# PCB_SCH_Right_Sub.net
KiCad netlist of a schematic drawn in EasyEDA Pro
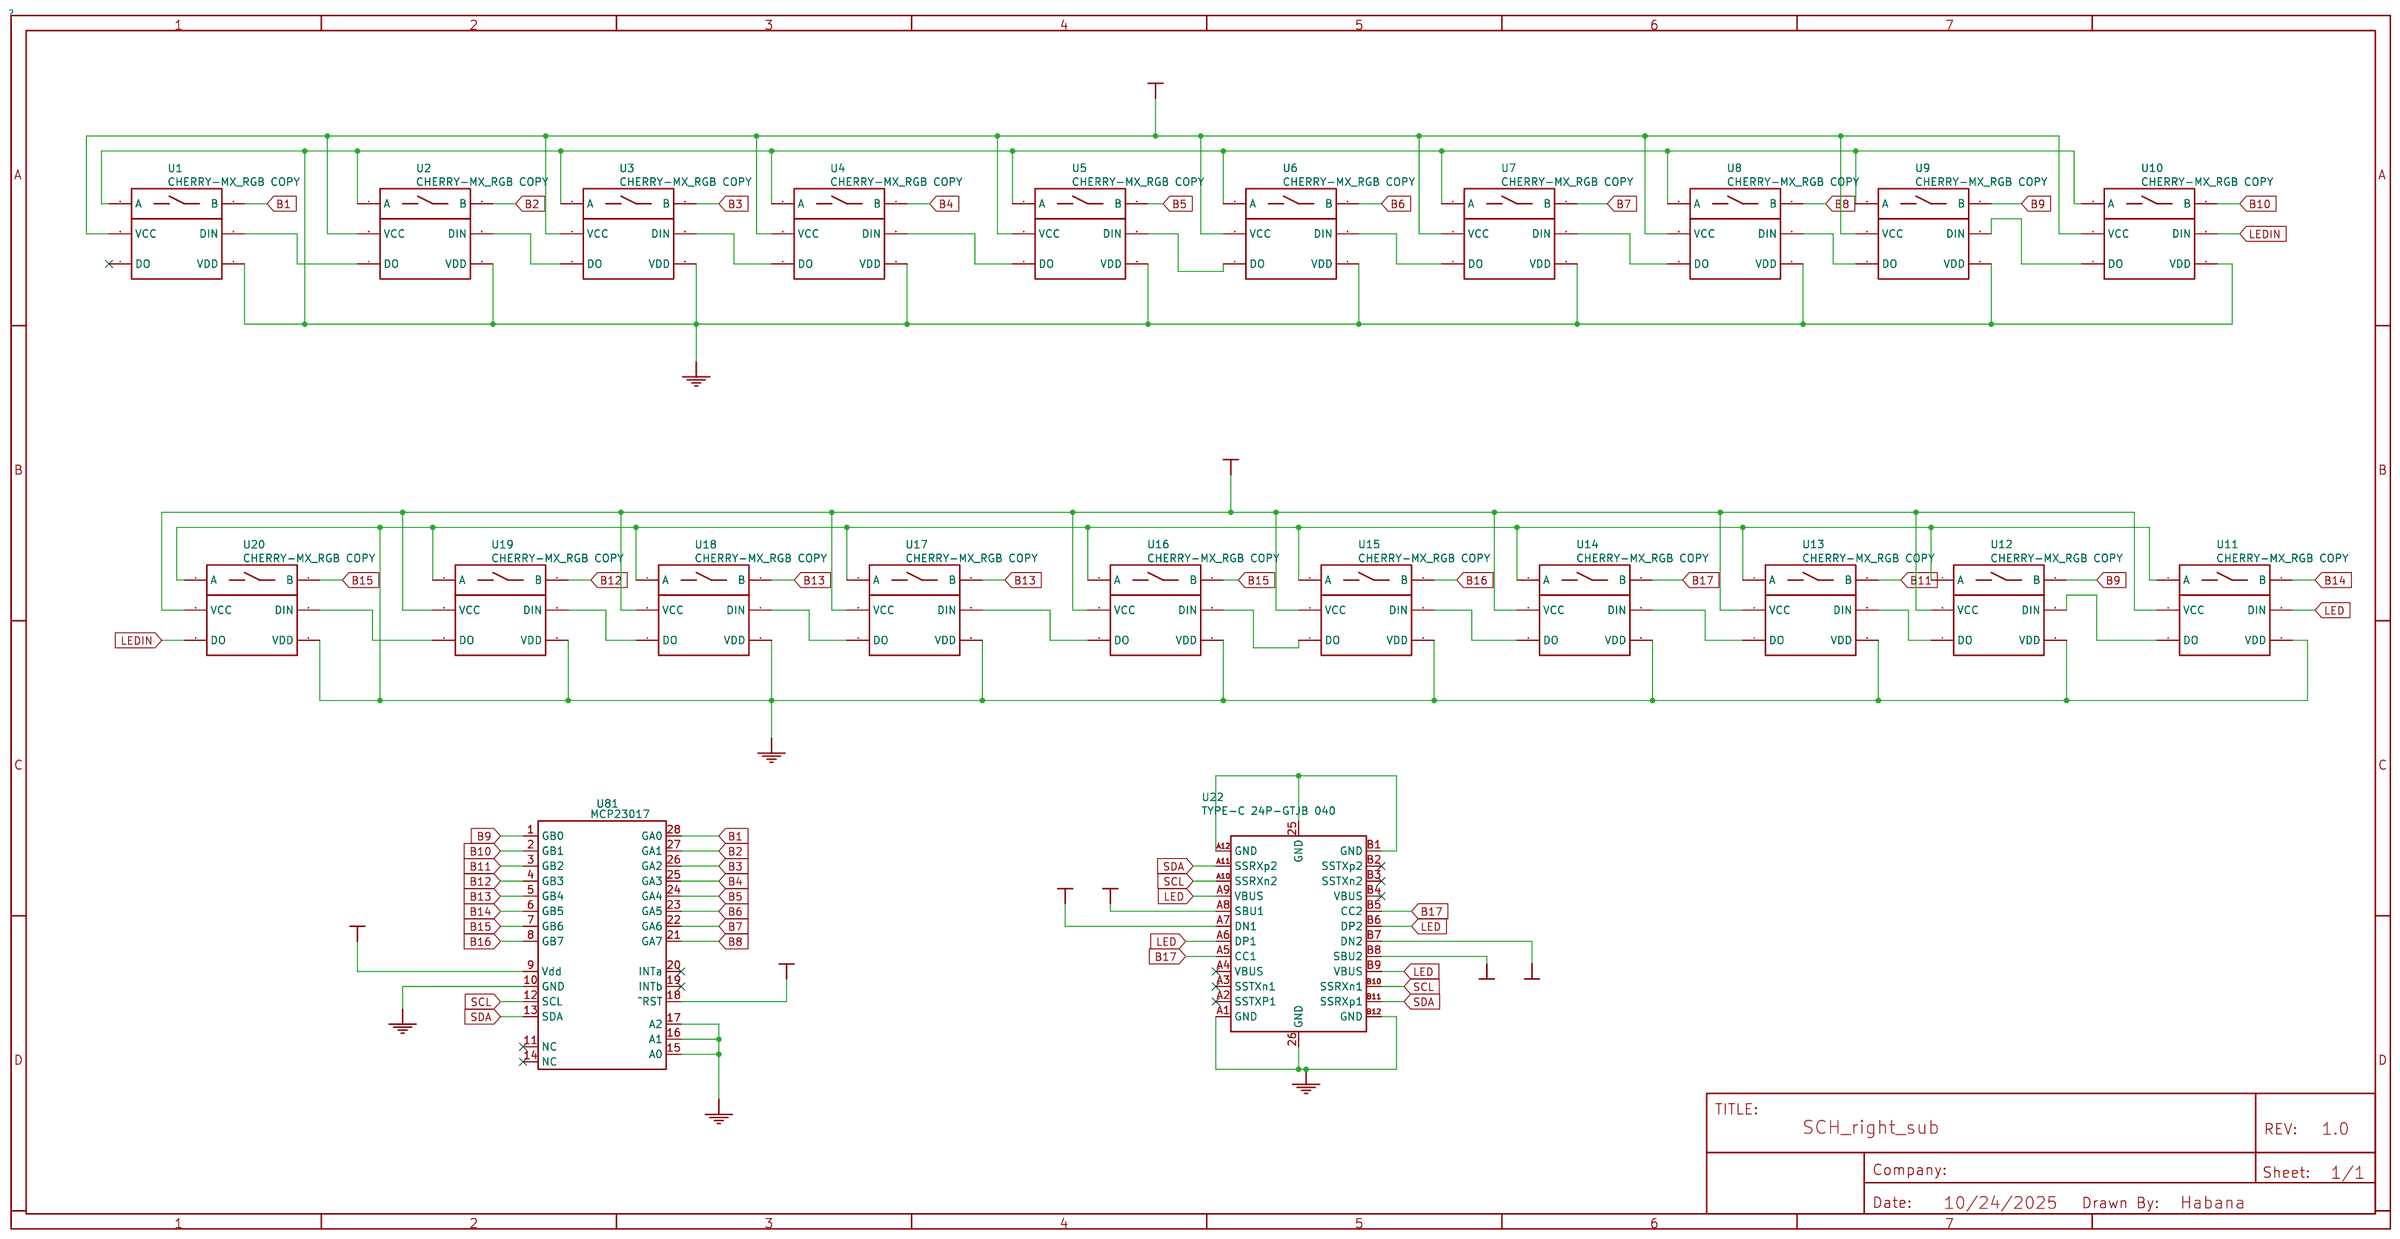
[diagram p0: schematic sheet]

(export (version "E")
  (design (tool "Eeschema 10.0.6"))
  (components
    (comp (ref "U1")
      (value "CHERRY-MX_RGB COPY")
      (fields (field (name "Contributor") "unrealin01"))
      (libsource (lib "easyedapro") (part "CHERRY-MX_RGB COPY"))
    )
    (comp (ref "U2")
      (value "CHERRY-MX_RGB COPY")
      (fields (field (name "Contributor") "unrealin01"))
      (libsource (lib "easyedapro") (part "CHERRY-MX_RGB COPY"))
    )
    (comp (ref "U3")
      (value "CHERRY-MX_RGB COPY")
      (fields (field (name "Contributor") "unrealin01"))
      (libsource (lib "easyedapro") (part "CHERRY-MX_RGB COPY"))
    )
    (comp (ref "U4")
      (value "CHERRY-MX_RGB COPY")
      (fields (field (name "Contributor") "unrealin01"))
      (libsource (lib "easyedapro") (part "CHERRY-MX_RGB COPY"))
    )
    (comp (ref "U5")
      (value "CHERRY-MX_RGB COPY")
      (fields (field (name "Contributor") "unrealin01"))
      (libsource (lib "easyedapro") (part "CHERRY-MX_RGB COPY"))
    )
    (comp (ref "U6")
      (value "CHERRY-MX_RGB COPY")
      (fields (field (name "Contributor") "unrealin01"))
      (libsource (lib "easyedapro") (part "CHERRY-MX_RGB COPY"))
    )
    (comp (ref "U7")
      (value "CHERRY-MX_RGB COPY")
      (fields (field (name "Contributor") "unrealin01"))
      (libsource (lib "easyedapro") (part "CHERRY-MX_RGB COPY"))
    )
    (comp (ref "U8")
      (value "CHERRY-MX_RGB COPY")
      (fields (field (name "Contributor") "unrealin01"))
      (libsource (lib "easyedapro") (part "CHERRY-MX_RGB COPY"))
    )
    (comp (ref "U9")
      (value "CHERRY-MX_RGB COPY")
      (fields (field (name "Contributor") "unrealin01"))
      (libsource (lib "easyedapro") (part "CHERRY-MX_RGB COPY"))
    )
    (comp (ref "U10")
      (value "CHERRY-MX_RGB COPY")
      (fields (field (name "Contributor") "unrealin01"))
      (libsource (lib "easyedapro") (part "CHERRY-MX_RGB COPY"))
    )
    (comp (ref "U11")
      (value "CHERRY-MX_RGB COPY")
      (fields (field (name "Contributor") "unrealin01"))
      (libsource (lib "easyedapro") (part "CHERRY-MX_RGB COPY"))
    )
    (comp (ref "U12")
      (value "CHERRY-MX_RGB COPY")
      (fields (field (name "Contributor") "unrealin01"))
      (libsource (lib "easyedapro") (part "CHERRY-MX_RGB COPY"))
    )
    (comp (ref "U13")
      (value "CHERRY-MX_RGB COPY")
      (fields (field (name "Contributor") "unrealin01"))
      (libsource (lib "easyedapro") (part "CHERRY-MX_RGB COPY"))
    )
    (comp (ref "U14")
      (value "CHERRY-MX_RGB COPY")
      (fields (field (name "Contributor") "unrealin01"))
      (libsource (lib "easyedapro") (part "CHERRY-MX_RGB COPY"))
    )
    (comp (ref "U15")
      (value "CHERRY-MX_RGB COPY")
      (fields (field (name "Contributor") "unrealin01"))
      (libsource (lib "easyedapro") (part "CHERRY-MX_RGB COPY"))
    )
    (comp (ref "U16")
      (value "CHERRY-MX_RGB COPY")
      (fields (field (name "Contributor") "unrealin01"))
      (libsource (lib "easyedapro") (part "CHERRY-MX_RGB COPY"))
    )
    (comp (ref "U17")
      (value "CHERRY-MX_RGB COPY")
      (fields (field (name "Contributor") "unrealin01"))
      (libsource (lib "easyedapro") (part "CHERRY-MX_RGB COPY"))
    )
    (comp (ref "U18")
      (value "CHERRY-MX_RGB COPY")
      (fields (field (name "Contributor") "unrealin01"))
      (libsource (lib "easyedapro") (part "CHERRY-MX_RGB COPY"))
    )
    (comp (ref "U19")
      (value "CHERRY-MX_RGB COPY")
      (fields (field (name "Contributor") "unrealin01"))
      (libsource (lib "easyedapro") (part "CHERRY-MX_RGB COPY"))
    )
    (comp (ref "U20")
      (value "CHERRY-MX_RGB COPY")
      (fields (field (name "Contributor") "unrealin01"))
      (libsource (lib "easyedapro") (part "CHERRY-MX_RGB COPY"))
    )
    (comp (ref "U22")
      (value "TYPE-C 24P-GTJB 040")
      (footprint "easyedapro:USB-C-SMD_TYPE-C-24P-GTJB-040")
      (fields (field (name "Manufacturer") "SHOU HAN(首韩)") (field (name "Contributor") "lcsc"))
      (libsource (lib "easyedapro") (part "TYPE-C 24P-GTJB 040"))
    )
    (comp (ref "U81")
      (value "MCP23017")
      (fields (field (name "Contributor") "tsvstar"))
      (libsource (lib "easyedapro") (part "MCP23017"))
    )
  )
  (nets
    (net (code "1") (name "+5V") (class "Default")
      (node (ref "U1") (pin "3") (pinfunction "VCC_3") (pintype "unspecified"))
      (node (ref "U10") (pin "3") (pinfunction "VCC_3") (pintype "unspecified"))
      (node (ref "U11") (pin "3") (pinfunction "VCC_3") (pintype "unspecified"))
      (node (ref "U12") (pin "3") (pinfunction "VCC_3") (pintype "unspecified"))
      (node (ref "U13") (pin "3") (pinfunction "VCC_3") (pintype "unspecified"))
      (node (ref "U14") (pin "3") (pinfunction "VCC_3") (pintype "unspecified"))
      (node (ref "U15") (pin "3") (pinfunction "VCC_3") (pintype "unspecified"))
      (node (ref "U16") (pin "3") (pinfunction "VCC_3") (pintype "unspecified"))
      (node (ref "U17") (pin "3") (pinfunction "VCC_3") (pintype "unspecified"))
      (node (ref "U18") (pin "3") (pinfunction "VCC_3") (pintype "unspecified"))
      (node (ref "U19") (pin "3") (pinfunction "VCC_3") (pintype "unspecified"))
      (node (ref "U2") (pin "3") (pinfunction "VCC_3") (pintype "unspecified"))
      (node (ref "U20") (pin "3") (pinfunction "VCC_3") (pintype "unspecified"))
      (node (ref "U22") (pin "A8") (pinfunction "SBU1_A8") (pintype "unspecified"))
      (node (ref "U22") (pin "B8") (pinfunction "SBU2_B8") (pintype "unspecified"))
      (node (ref "U3") (pin "3") (pinfunction "VCC_3") (pintype "unspecified"))
      (node (ref "U4") (pin "3") (pinfunction "VCC_3") (pintype "unspecified"))
      (node (ref "U5") (pin "3") (pinfunction "VCC_3") (pintype "unspecified"))
      (node (ref "U6") (pin "3") (pinfunction "VCC_3") (pintype "unspecified"))
      (node (ref "U7") (pin "3") (pinfunction "VCC_3") (pintype "unspecified"))
      (node (ref "U8") (pin "3") (pinfunction "VCC_3") (pintype "unspecified"))
      (node (ref "U9") (pin "3") (pinfunction "VCC_3") (pintype "unspecified"))
    )
    (net (code "2") (name "B1") (class "Default")
      (node (ref "U1") (pin "2") (pinfunction "B_2") (pintype "unspecified"))
      (node (ref "U81") (pin "28") (pinfunction "GA0_28") (pintype "unspecified"))
    )
    (net (code "3") (name "B2") (class "Default")
      (node (ref "U2") (pin "2") (pinfunction "B_2") (pintype "unspecified"))
      (node (ref "U81") (pin "27") (pinfunction "GA1_27") (pintype "unspecified"))
    )
    (net (code "4") (name "B3") (class "Default")
      (node (ref "U3") (pin "2") (pinfunction "B_2") (pintype "unspecified"))
      (node (ref "U81") (pin "26") (pinfunction "GA2_26") (pintype "unspecified"))
    )
    (net (code "5") (name "B4") (class "Default")
      (node (ref "U4") (pin "2") (pinfunction "B_2") (pintype "unspecified"))
      (node (ref "U81") (pin "25") (pinfunction "GA3_25") (pintype "unspecified"))
    )
    (net (code "6") (name "B5") (class "Default")
      (node (ref "U5") (pin "2") (pinfunction "B_2") (pintype "unspecified"))
      (node (ref "U81") (pin "24") (pinfunction "GA4_24") (pintype "unspecified"))
    )
    (net (code "7") (name "B6") (class "Default")
      (node (ref "U6") (pin "2") (pinfunction "B_2") (pintype "unspecified"))
      (node (ref "U81") (pin "23") (pinfunction "GA5_23") (pintype "unspecified"))
    )
    (net (code "8") (name "B7") (class "Default")
      (node (ref "U7") (pin "2") (pinfunction "B_2") (pintype "unspecified"))
      (node (ref "U81") (pin "22") (pinfunction "GA6_22") (pintype "unspecified"))
    )
    (net (code "9") (name "B8") (class "Default")
      (node (ref "U8") (pin "2") (pinfunction "B_2") (pintype "unspecified"))
      (node (ref "U81") (pin "21") (pinfunction "GA7_21") (pintype "unspecified"))
    )
    (net (code "10") (name "B9") (class "Default")
      (node (ref "U12") (pin "2") (pinfunction "B_2") (pintype "unspecified"))
      (node (ref "U81") (pin "1") (pinfunction "GB0_1") (pintype "unspecified"))
      (node (ref "U9") (pin "2") (pinfunction "B_2") (pintype "unspecified"))
    )
    (net (code "11") (name "B10") (class "Default")
      (node (ref "U10") (pin "2") (pinfunction "B_2") (pintype "unspecified"))
      (node (ref "U81") (pin "2") (pinfunction "GB1_2") (pintype "unspecified"))
    )
    (net (code "12") (name "B11") (class "Default")
      (node (ref "U13") (pin "2") (pinfunction "B_2") (pintype "unspecified"))
      (node (ref "U81") (pin "3") (pinfunction "GB2_3") (pintype "unspecified"))
    )
    (net (code "13") (name "B12") (class "Default")
      (node (ref "U19") (pin "2") (pinfunction "B_2") (pintype "unspecified"))
      (node (ref "U81") (pin "4") (pinfunction "GB3_4") (pintype "unspecified"))
    )
    (net (code "14") (name "B13") (class "Default")
      (node (ref "U17") (pin "2") (pinfunction "B_2") (pintype "unspecified"))
      (node (ref "U18") (pin "2") (pinfunction "B_2") (pintype "unspecified"))
      (node (ref "U81") (pin "5") (pinfunction "GB4_5") (pintype "unspecified"))
    )
    (net (code "15") (name "B14") (class "Default")
      (node (ref "U11") (pin "2") (pinfunction "B_2") (pintype "unspecified"))
      (node (ref "U81") (pin "6") (pinfunction "GB5_6") (pintype "unspecified"))
    )
    (net (code "16") (name "B15") (class "Default")
      (node (ref "U16") (pin "2") (pinfunction "B_2") (pintype "unspecified"))
      (node (ref "U20") (pin "2") (pinfunction "B_2") (pintype "unspecified"))
      (node (ref "U81") (pin "7") (pinfunction "GB6_7") (pintype "unspecified"))
    )
    (net (code "17") (name "B16") (class "Default")
      (node (ref "U15") (pin "2") (pinfunction "B_2") (pintype "unspecified"))
      (node (ref "U81") (pin "8") (pinfunction "GB7_8") (pintype "unspecified"))
    )
    (net (code "18") (name "B17") (class "Default")
      (node (ref "U14") (pin "2") (pinfunction "B_2") (pintype "unspecified"))
      (node (ref "U22") (pin "A5") (pinfunction "CC1_A5") (pintype "unspecified"))
      (node (ref "U22") (pin "B5") (pinfunction "CC2_B5") (pintype "unspecified"))
    )
    (net (code "19") (name "GND") (class "Default")
      (node (ref "U1") (pin "1") (pinfunction "A_1") (pintype "unspecified"))
      (node (ref "U1") (pin "5") (pinfunction "VDD_5") (pintype "unspecified"))
      (node (ref "U10") (pin "1") (pinfunction "A_1") (pintype "unspecified"))
      (node (ref "U10") (pin "5") (pinfunction "VDD_5") (pintype "unspecified"))
      (node (ref "U11") (pin "1") (pinfunction "A_1") (pintype "unspecified"))
      (node (ref "U11") (pin "5") (pinfunction "VDD_5") (pintype "unspecified"))
      (node (ref "U12") (pin "1") (pinfunction "A_1") (pintype "unspecified"))
      (node (ref "U12") (pin "5") (pinfunction "VDD_5") (pintype "unspecified"))
      (node (ref "U13") (pin "1") (pinfunction "A_1") (pintype "unspecified"))
      (node (ref "U13") (pin "5") (pinfunction "VDD_5") (pintype "unspecified"))
      (node (ref "U14") (pin "1") (pinfunction "A_1") (pintype "unspecified"))
      (node (ref "U14") (pin "5") (pinfunction "VDD_5") (pintype "unspecified"))
      (node (ref "U15") (pin "1") (pinfunction "A_1") (pintype "unspecified"))
      (node (ref "U15") (pin "5") (pinfunction "VDD_5") (pintype "unspecified"))
      (node (ref "U16") (pin "1") (pinfunction "A_1") (pintype "unspecified"))
      (node (ref "U16") (pin "5") (pinfunction "VDD_5") (pintype "unspecified"))
      (node (ref "U17") (pin "1") (pinfunction "A_1") (pintype "unspecified"))
      (node (ref "U17") (pin "5") (pinfunction "VDD_5") (pintype "unspecified"))
      (node (ref "U18") (pin "1") (pinfunction "A_1") (pintype "unspecified"))
      (node (ref "U18") (pin "5") (pinfunction "VDD_5") (pintype "unspecified"))
      (node (ref "U19") (pin "1") (pinfunction "A_1") (pintype "unspecified"))
      (node (ref "U19") (pin "5") (pinfunction "VDD_5") (pintype "unspecified"))
      (node (ref "U2") (pin "1") (pinfunction "A_1") (pintype "unspecified"))
      (node (ref "U2") (pin "5") (pinfunction "VDD_5") (pintype "unspecified"))
      (node (ref "U20") (pin "1") (pinfunction "A_1") (pintype "unspecified"))
      (node (ref "U20") (pin "5") (pinfunction "VDD_5") (pintype "unspecified"))
      (node (ref "U22") (pin "26") (pinfunction "GND_26") (pintype "unspecified"))
      (node (ref "U22") (pin "A1") (pinfunction "GND_A1") (pintype "unspecified"))
      (node (ref "U22") (pin "B12") (pinfunction "GND_B12") (pintype "unspecified"))
      (node (ref "U3") (pin "1") (pinfunction "A_1") (pintype "unspecified"))
      (node (ref "U3") (pin "5") (pinfunction "VDD_5") (pintype "unspecified"))
      (node (ref "U4") (pin "1") (pinfunction "A_1") (pintype "unspecified"))
      (node (ref "U4") (pin "5") (pinfunction "VDD_5") (pintype "unspecified"))
      (node (ref "U5") (pin "1") (pinfunction "A_1") (pintype "unspecified"))
      (node (ref "U5") (pin "5") (pinfunction "VDD_5") (pintype "unspecified"))
      (node (ref "U6") (pin "1") (pinfunction "A_1") (pintype "unspecified"))
      (node (ref "U6") (pin "5") (pinfunction "VDD_5") (pintype "unspecified"))
      (node (ref "U7") (pin "1") (pinfunction "A_1") (pintype "unspecified"))
      (node (ref "U7") (pin "5") (pinfunction "VDD_5") (pintype "unspecified"))
      (node (ref "U8") (pin "1") (pinfunction "A_1") (pintype "unspecified"))
      (node (ref "U8") (pin "5") (pinfunction "VDD_5") (pintype "unspecified"))
      (node (ref "U81") (pin "10") (pinfunction "GND_10") (pintype "unspecified"))
      (node (ref "U81") (pin "15") (pinfunction "A0_15") (pintype "unspecified"))
      (node (ref "U81") (pin "16") (pinfunction "A1_16") (pintype "unspecified"))
      (node (ref "U81") (pin "17") (pinfunction "A2_17") (pintype "unspecified"))
      (node (ref "U9") (pin "1") (pinfunction "A_1") (pintype "unspecified"))
      (node (ref "U9") (pin "5") (pinfunction "VDD_5") (pintype "unspecified"))
    )
    (net (code "20") (name "LED") (class "Default")
      (node (ref "U11") (pin "6") (pinfunction "DIN_6") (pintype "unspecified"))
      (node (ref "U22") (pin "A6") (pinfunction "DP1_A6") (pintype "unspecified"))
      (node (ref "U22") (pin "A9") (pinfunction "VBUS_A9") (pintype "unspecified"))
      (node (ref "U22") (pin "B6") (pinfunction "DP2_B6") (pintype "unspecified"))
      (node (ref "U22") (pin "B9") (pinfunction "VBUS_B9") (pintype "unspecified"))
    )
    (net (code "21") (name "LEDIN") (class "Default")
      (node (ref "U10") (pin "6") (pinfunction "DIN_6") (pintype "unspecified"))
      (node (ref "U20") (pin "4") (pinfunction "DO_4") (pintype "unspecified"))
    )
    (net (code "22") (name "Net-(U1-DIN)") (class "Default")
      (node (ref "U1") (pin "6") (pinfunction "DIN_6") (pintype "unspecified"))
      (node (ref "U2") (pin "4") (pinfunction "DO_4") (pintype "unspecified"))
    )
    (net (code "23") (name "Net-(U2-DIN)") (class "Default")
      (node (ref "U2") (pin "6") (pinfunction "DIN_6") (pintype "unspecified"))
      (node (ref "U3") (pin "4") (pinfunction "DO_4") (pintype "unspecified"))
    )
    (net (code "24") (name "Net-(U3-DIN)") (class "Default")
      (node (ref "U3") (pin "6") (pinfunction "DIN_6") (pintype "unspecified"))
      (node (ref "U4") (pin "4") (pinfunction "DO_4") (pintype "unspecified"))
    )
    (net (code "25") (name "Net-(U4-DIN)") (class "Default")
      (node (ref "U4") (pin "6") (pinfunction "DIN_6") (pintype "unspecified"))
      (node (ref "U5") (pin "4") (pinfunction "DO_4") (pintype "unspecified"))
    )
    (net (code "26") (name "Net-(U5-DIN)") (class "Default")
      (node (ref "U5") (pin "6") (pinfunction "DIN_6") (pintype "unspecified"))
      (node (ref "U6") (pin "4") (pinfunction "DO_4") (pintype "unspecified"))
    )
    (net (code "27") (name "Net-(U6-DIN)") (class "Default")
      (node (ref "U6") (pin "6") (pinfunction "DIN_6") (pintype "unspecified"))
      (node (ref "U7") (pin "4") (pinfunction "DO_4") (pintype "unspecified"))
    )
    (net (code "28") (name "Net-(U7-DIN)") (class "Default")
      (node (ref "U7") (pin "6") (pinfunction "DIN_6") (pintype "unspecified"))
      (node (ref "U8") (pin "4") (pinfunction "DO_4") (pintype "unspecified"))
    )
    (net (code "29") (name "Net-(U8-DIN)") (class "Default")
      (node (ref "U8") (pin "6") (pinfunction "DIN_6") (pintype "unspecified"))
      (node (ref "U9") (pin "4") (pinfunction "DO_4") (pintype "unspecified"))
    )
    (net (code "30") (name "Net-(U10-DO)") (class "Default")
      (node (ref "U10") (pin "4") (pinfunction "DO_4") (pintype "unspecified"))
      (node (ref "U9") (pin "6") (pinfunction "DIN_6") (pintype "unspecified"))
    )
    (net (code "31") (name "Net-(U11-DO)") (class "Default")
      (node (ref "U11") (pin "4") (pinfunction "DO_4") (pintype "unspecified"))
      (node (ref "U12") (pin "6") (pinfunction "DIN_6") (pintype "unspecified"))
    )
    (net (code "32") (name "Net-(U12-DO)") (class "Default")
      (node (ref "U12") (pin "4") (pinfunction "DO_4") (pintype "unspecified"))
      (node (ref "U13") (pin "6") (pinfunction "DIN_6") (pintype "unspecified"))
    )
    (net (code "33") (name "Net-(U13-DO)") (class "Default")
      (node (ref "U13") (pin "4") (pinfunction "DO_4") (pintype "unspecified"))
      (node (ref "U14") (pin "6") (pinfunction "DIN_6") (pintype "unspecified"))
    )
    (net (code "34") (name "Net-(U14-DO)") (class "Default")
      (node (ref "U14") (pin "4") (pinfunction "DO_4") (pintype "unspecified"))
      (node (ref "U15") (pin "6") (pinfunction "DIN_6") (pintype "unspecified"))
    )
    (net (code "35") (name "Net-(U15-DO)") (class "Default")
      (node (ref "U15") (pin "4") (pinfunction "DO_4") (pintype "unspecified"))
      (node (ref "U16") (pin "6") (pinfunction "DIN_6") (pintype "unspecified"))
    )
    (net (code "36") (name "Net-(U16-DO)") (class "Default")
      (node (ref "U16") (pin "4") (pinfunction "DO_4") (pintype "unspecified"))
      (node (ref "U17") (pin "6") (pinfunction "DIN_6") (pintype "unspecified"))
    )
    (net (code "37") (name "Net-(U17-DO)") (class "Default")
      (node (ref "U17") (pin "4") (pinfunction "DO_4") (pintype "unspecified"))
      (node (ref "U18") (pin "6") (pinfunction "DIN_6") (pintype "unspecified"))
    )
    (net (code "38") (name "Net-(U18-DO)") (class "Default")
      (node (ref "U18") (pin "4") (pinfunction "DO_4") (pintype "unspecified"))
      (node (ref "U19") (pin "6") (pinfunction "DIN_6") (pintype "unspecified"))
    )
    (net (code "39") (name "Net-(U19-DO)") (class "Default")
      (node (ref "U19") (pin "4") (pinfunction "DO_4") (pintype "unspecified"))
      (node (ref "U20") (pin "6") (pinfunction "DIN_6") (pintype "unspecified"))
    )
    (net (code "40") (name "Net-(U22-GND-Pad25)") (class "Default")
      (node (ref "U22") (pin "25") (pinfunction "GND_25") (pintype "unspecified"))
      (node (ref "U22") (pin "A12") (pinfunction "GND_A12") (pintype "unspecified"))
      (node (ref "U22") (pin "B1") (pinfunction "GND_B1") (pintype "unspecified"))
    )
    (net (code "41") (name "SCL") (class "Default")
      (node (ref "U22") (pin "A10") (pinfunction "SSRXn2_A10") (pintype "unspecified"))
      (node (ref "U22") (pin "B10") (pinfunction "SSRXn1_B10") (pintype "unspecified"))
      (node (ref "U81") (pin "12") (pinfunction "SCL_12") (pintype "unspecified"))
    )
    (net (code "42") (name "SDA") (class "Default")
      (node (ref "U22") (pin "A11") (pinfunction "SSRXp2_A11") (pintype "unspecified"))
      (node (ref "U22") (pin "B11") (pinfunction "SSRXp1_B11") (pintype "unspecified"))
      (node (ref "U81") (pin "13") (pinfunction "SDA_13") (pintype "unspecified"))
    )
    (net (code "43") (name "VCC") (class "Default")
      (node (ref "U22") (pin "A7") (pinfunction "DN1_A7") (pintype "unspecified"))
      (node (ref "U22") (pin "B7") (pinfunction "DN2_B7") (pintype "unspecified"))
      (node (ref "U81") (pin "18") (pinfunction "^RST_18") (pintype "unspecified"))
      (node (ref "U81") (pin "9") (pinfunction "Vdd_9") (pintype "unspecified"))
    )
    (net (code "44") (name "unconnected-(U1-DO-Pad4)") (class "Default")
      (node (ref "U1") (pin "4") (pinfunction "DO_4") (pintype "unspecified+no_connect"))
    )
    (net (code "45") (name "unconnected-(U22-SSTXP1-PadA2)") (class "Default")
      (node (ref "U22") (pin "A2") (pinfunction "SSTXP1_A2") (pintype "unspecified+no_connect"))
    )
    (net (code "46") (name "unconnected-(U22-SSTXn1-PadA3)") (class "Default")
      (node (ref "U22") (pin "A3") (pinfunction "SSTXn1_A3") (pintype "unspecified+no_connect"))
    )
    (net (code "47") (name "unconnected-(U22-SSTXn2-PadB3)") (class "Default")
      (node (ref "U22") (pin "B3") (pinfunction "SSTXn2_B3") (pintype "unspecified+no_connect"))
    )
    (net (code "48") (name "unconnected-(U22-SSTXp2-PadB2)") (class "Default")
      (node (ref "U22") (pin "B2") (pinfunction "SSTXp2_B2") (pintype "unspecified+no_connect"))
    )
    (net (code "49") (name "unconnected-(U22-VBUS-PadA4)") (class "Default")
      (node (ref "U22") (pin "A4") (pinfunction "VBUS_A4") (pintype "unspecified+no_connect"))
    )
    (net (code "50") (name "unconnected-(U22-VBUS-PadB4)") (class "Default")
      (node (ref "U22") (pin "B4") (pinfunction "VBUS_B4") (pintype "unspecified+no_connect"))
    )
    (net (code "51") (name "unconnected-(U81-INTa-Pad20)") (class "Default")
      (node (ref "U81") (pin "20") (pinfunction "INTa_20") (pintype "unspecified+no_connect"))
    )
    (net (code "52") (name "unconnected-(U81-INTb-Pad19)") (class "Default")
      (node (ref "U81") (pin "19") (pinfunction "INTb_19") (pintype "unspecified+no_connect"))
    )
    (net (code "53") (name "unconnected-(U81-NC-Pad11)") (class "Default")
      (node (ref "U81") (pin "11") (pinfunction "NC_11") (pintype "unspecified+no_connect"))
    )
    (net (code "54") (name "unconnected-(U81-NC-Pad14)") (class "Default")
      (node (ref "U81") (pin "14") (pinfunction "NC_14") (pintype "unspecified+no_connect"))
    )
  )
)
